# Sheet1.net
KiCad netlist of a schematic drawn in Altium Designer
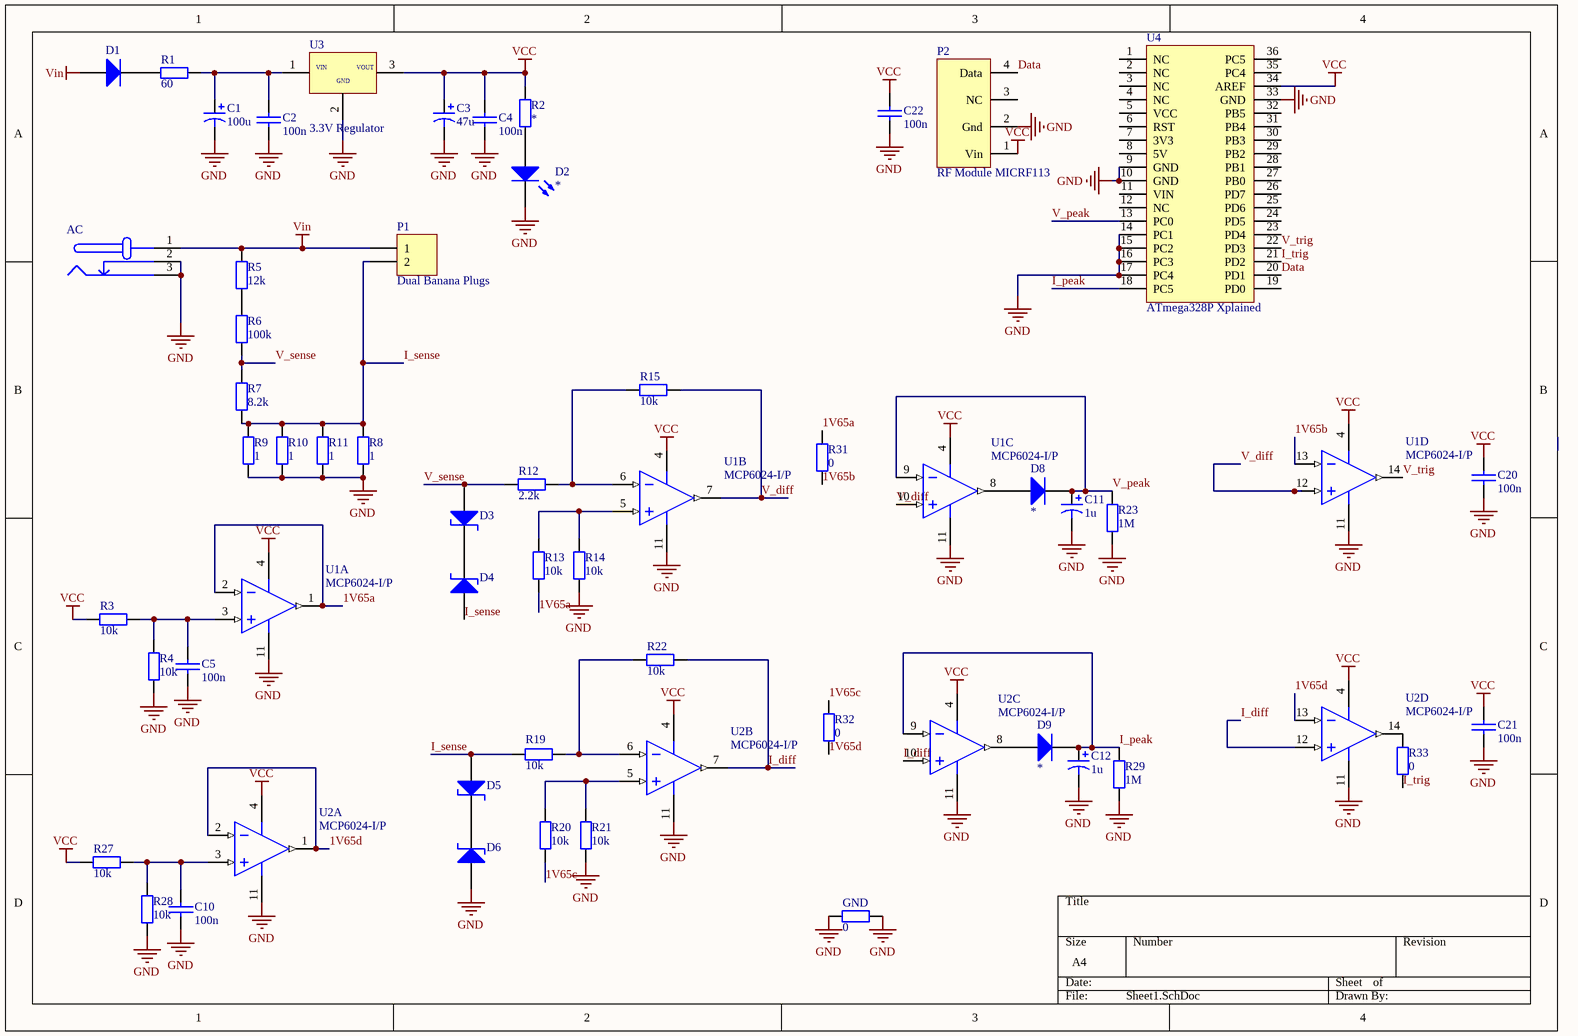
[diagram p0: Sheet1.SchDoc]

(export (version "E")
  (design (tool "Eeschema 10.0.6"))
  (components
    (comp (ref "AC")
      (value "~")
      (footprint "AC-Socket")
      (description "DC socket")
      (libsource (lib "EE209_SCHLibrary") (part "AC Input"))
    )
    (comp (ref "C1")
      (value "100u")
      (footprint "CAP-RAD-3mm Pitch")
      (description "Polarized Capacitor (Axial)")
      (fields (field (name "PUBLISHER") "Altium Limited"))
      (libsource (lib "EE209_SCHLibrary") (part "Cap Pol (22uF-100uF)"))
    )
    (comp (ref "C2")
      (value "100n")
      (footprint "FILM CAP-0.2")
      (description "Capacitor Non Polarised Through Hole")
      (libsource (lib "EE209_SCHLibrary") (part "CAP"))
    )
    (comp (ref "C3")
      (value "47u")
      (footprint "CAP-RAD-3mm Pitch")
      (description "Polarized Capacitor (Axial)")
      (fields (field (name "PUBLISHER") "Altium Limited"))
      (libsource (lib "EE209_SCHLibrary") (part "Cap Pol (22uF-100uF)"))
    )
    (comp (ref "C4")
      (value "100n")
      (footprint "FILM CAP-0.2")
      (description "Capacitor Non Polarised Through Hole")
      (libsource (lib "EE209_SCHLibrary") (part "CAP"))
    )
    (comp (ref "C5")
      (value "100n")
      (footprint "FILM CAP-0.2")
      (description "Capacitor Non Polarised Through Hole")
      (libsource (lib "EE209_SCHLibrary") (part "CAP"))
    )
    (comp (ref "C10")
      (value "100n")
      (footprint "FILM CAP-0.2")
      (description "Capacitor Non Polarised Through Hole")
      (libsource (lib "EE209_SCHLibrary") (part "CAP"))
    )
    (comp (ref "C11")
      (value "1u")
      (footprint "CAP-RAD-2mm Pitch")
      (description "Polarized Capacitor (Axial)")
      (fields (field (name "PUBLISHER") "Altium Limited"))
      (libsource (lib "EE209_SCHLibrary") (part "Cap Pol (1uF-10uF)"))
    )
    (comp (ref "C12")
      (value "1u")
      (footprint "CAP-RAD-2mm Pitch")
      (description "Polarized Capacitor (Axial)")
      (fields (field (name "PUBLISHER") "Altium Limited"))
      (libsource (lib "EE209_SCHLibrary") (part "Cap Pol (1uF-10uF)"))
    )
    (comp (ref "C20")
      (value "100n")
      (footprint "FILM CAP-0.2")
      (description "Capacitor Non Polarised Through Hole")
      (libsource (lib "EE209_SCHLibrary") (part "CAP"))
    )
    (comp (ref "C21")
      (value "100n")
      (footprint "FILM CAP-0.2")
      (description "Capacitor Non Polarised Through Hole")
      (libsource (lib "EE209_SCHLibrary") (part "CAP"))
    )
    (comp (ref "C22")
      (value "100n")
      (footprint "FILM CAP-0.2")
      (description "Capacitor Non Polarised Through Hole")
      (libsource (lib "EE209_SCHLibrary") (part "CAP"))
    )
    (comp (ref "D1")
      (value "~")
      (footprint "AXIAL-DIODE-0.4")
      (fields
        (field (name "MANUFACTURER") "Fairchild Semiconductor")
        (field (name "PUBLISHER") "Altium Limited")
      )
      (libsource (lib "EE209_SCHLibrary") (part "Diode"))
    )
    (comp (ref "D2")
      (value "*")
      (footprint "LED")
      (description "Typical GaAs LED")
      (fields (field (name "MANUFACTURER") "Generic Components") (field (name "PUBLISHER") "Altium Limited"))
      (libsource (lib "EE209_SCHLibrary") (part "LED"))
    )
    (comp (ref "D3")
      (value "~")
      (footprint "AXIAL-DIODE-0.4")
      (description "Zener Diode")
      (libsource (lib "EE209_SCHLibrary") (part "Zener"))
    )
    (comp (ref "D4")
      (value "~")
      (footprint "AXIAL-DIODE-0.4")
      (description "Zener Diode")
      (libsource (lib "EE209_SCHLibrary") (part "Zener"))
    )
    (comp (ref "D5")
      (value "~")
      (footprint "AXIAL-DIODE-0.4")
      (description "Zener Diode")
      (libsource (lib "EE209_SCHLibrary") (part "Zener"))
    )
    (comp (ref "D6")
      (value "~")
      (footprint "AXIAL-DIODE-0.4")
      (description "Zener Diode")
      (libsource (lib "EE209_SCHLibrary") (part "Zener"))
    )
    (comp (ref "D8")
      (value "*")
      (footprint "AXIAL-DIODE-0.4")
      (fields
        (field (name "MANUFACTURER") "Fairchild Semiconductor")
        (field (name "PUBLISHER") "Altium Limited")
      )
      (libsource (lib "EE209_SCHLibrary") (part "Diode"))
    )
    (comp (ref "D9")
      (value "*")
      (footprint "AXIAL-DIODE-0.4")
      (fields
        (field (name "MANUFACTURER") "Fairchild Semiconductor")
        (field (name "PUBLISHER") "Altium Limited")
      )
      (libsource (lib "EE209_SCHLibrary") (part "Diode"))
    )
    (comp (ref "GND")
      (value "0")
      (footprint "AXIAL-0.4")
      (description "Through Hole Resistor")
      (fields (field (name "PUBLISHER") "Altium Limited"))
      (libsource (lib "") (part "Res_1"))
    )
    (comp (ref "P1")
      (value "Dual Banana Plugs")
      (footprint "Dual Banana Plug")
      (description "M6 Holes")
      (fields (field (name "PUBLISHER") "Altium Limited"))
      (libsource (lib "EE209_SCHLibrary") (part "Dual Banana Plugs"))
    )
    (comp (ref "P2")
      (value "RF Module MICRF113")
      (footprint "MICRF113 TX")
      (description "Vertical Mount RF Module")
      (libsource (lib "EE209_SCHLibrary") (part "RF Module"))
    )
    (comp (ref "R1")
      (value "60")
      (footprint "AXIAL-0.4")
      (description "Through Hole Resistor")
      (fields (field (name "PUBLISHER") "Altium Limited"))
      (libsource (lib "") (part "Res_1"))
    )
    (comp (ref "R2")
      (value "*")
      (footprint "AXIAL-0.4")
      (description "Through Hole Resistor")
      (fields (field (name "PUBLISHER") "Altium Limited"))
      (libsource (lib "EE209_SCHLibrary") (part "Res"))
    )
    (comp (ref "R3")
      (value "10k")
      (footprint "AXIAL-0.4")
      (description "Through Hole Resistor")
      (fields (field (name "PUBLISHER") "Altium Limited"))
      (libsource (lib "") (part "Res_1"))
    )
    (comp (ref "R4")
      (value "10k")
      (footprint "AXIAL-0.4")
      (description "Through Hole Resistor")
      (fields (field (name "PUBLISHER") "Altium Limited"))
      (libsource (lib "EE209_SCHLibrary") (part "Res"))
    )
    (comp (ref "R5")
      (value "12k")
      (footprint "AXIAL-0.4")
      (description "Through Hole Resistor")
      (fields (field (name "PUBLISHER") "Altium Limited"))
      (libsource (lib "EE209_SCHLibrary") (part "Res"))
    )
    (comp (ref "R6")
      (value "100k")
      (footprint "AXIAL-0.4")
      (description "Through Hole Resistor")
      (fields (field (name "PUBLISHER") "Altium Limited"))
      (libsource (lib "EE209_SCHLibrary") (part "Res"))
    )
    (comp (ref "R7")
      (value "8.2k")
      (footprint "AXIAL-0.4")
      (description "Through Hole Resistor")
      (fields (field (name "PUBLISHER") "Altium Limited"))
      (libsource (lib "EE209_SCHLibrary") (part "Res"))
    )
    (comp (ref "R8")
      (value "1")
      (footprint "AXIAL-0.4")
      (description "Through Hole Resistor")
      (fields (field (name "PUBLISHER") "Altium Limited"))
      (libsource (lib "EE209_SCHLibrary") (part "Res"))
    )
    (comp (ref "R9")
      (value "1")
      (footprint "AXIAL-0.4")
      (description "Through Hole Resistor")
      (fields (field (name "PUBLISHER") "Altium Limited"))
      (libsource (lib "EE209_SCHLibrary") (part "Res"))
    )
    (comp (ref "R10")
      (value "1")
      (footprint "AXIAL-0.4")
      (description "Through Hole Resistor")
      (fields (field (name "PUBLISHER") "Altium Limited"))
      (libsource (lib "EE209_SCHLibrary") (part "Res"))
    )
    (comp (ref "R11")
      (value "1")
      (footprint "AXIAL-0.4")
      (description "Through Hole Resistor")
      (fields (field (name "PUBLISHER") "Altium Limited"))
      (libsource (lib "EE209_SCHLibrary") (part "Res"))
    )
    (comp (ref "R12")
      (value "2.2k")
      (footprint "AXIAL-0.4")
      (description "Through Hole Resistor")
      (fields (field (name "PUBLISHER") "Altium Limited"))
      (libsource (lib "") (part "Res_1"))
    )
    (comp (ref "R13")
      (value "10k")
      (footprint "AXIAL-0.4")
      (description "Through Hole Resistor")
      (fields (field (name "PUBLISHER") "Altium Limited"))
      (libsource (lib "EE209_SCHLibrary") (part "Res"))
    )
    (comp (ref "R14")
      (value "10k")
      (footprint "AXIAL-0.4")
      (description "Through Hole Resistor")
      (fields (field (name "PUBLISHER") "Altium Limited"))
      (libsource (lib "EE209_SCHLibrary") (part "Res"))
    )
    (comp (ref "R15")
      (value "10k")
      (footprint "AXIAL-0.4")
      (description "Through Hole Resistor")
      (fields (field (name "PUBLISHER") "Altium Limited"))
      (libsource (lib "") (part "Res_1"))
    )
    (comp (ref "R19")
      (value "10k")
      (footprint "AXIAL-0.4")
      (description "Through Hole Resistor")
      (fields (field (name "PUBLISHER") "Altium Limited"))
      (libsource (lib "") (part "Res_1"))
    )
    (comp (ref "R20")
      (value "10k")
      (footprint "AXIAL-0.4")
      (description "Through Hole Resistor")
      (fields (field (name "PUBLISHER") "Altium Limited"))
      (libsource (lib "EE209_SCHLibrary") (part "Res"))
    )
    (comp (ref "R21")
      (value "10k")
      (footprint "AXIAL-0.4")
      (description "Through Hole Resistor")
      (fields (field (name "PUBLISHER") "Altium Limited"))
      (libsource (lib "EE209_SCHLibrary") (part "Res"))
    )
    (comp (ref "R22")
      (value "10k")
      (footprint "AXIAL-0.4")
      (description "Through Hole Resistor")
      (fields (field (name "PUBLISHER") "Altium Limited"))
      (libsource (lib "") (part "Res_1"))
    )
    (comp (ref "R23")
      (value "1M")
      (footprint "AXIAL-0.4")
      (description "Through Hole Resistor")
      (fields (field (name "PUBLISHER") "Altium Limited"))
      (libsource (lib "EE209_SCHLibrary") (part "Res"))
    )
    (comp (ref "R27")
      (value "10k")
      (footprint "AXIAL-0.4")
      (description "Through Hole Resistor")
      (fields (field (name "PUBLISHER") "Altium Limited"))
      (libsource (lib "") (part "Res_1"))
    )
    (comp (ref "R28")
      (value "10k")
      (footprint "AXIAL-0.4")
      (description "Through Hole Resistor")
      (fields (field (name "PUBLISHER") "Altium Limited"))
      (libsource (lib "EE209_SCHLibrary") (part "Res"))
    )
    (comp (ref "R29")
      (value "1M")
      (footprint "AXIAL-0.4")
      (description "Through Hole Resistor")
      (fields (field (name "PUBLISHER") "Altium Limited"))
      (libsource (lib "EE209_SCHLibrary") (part "Res"))
    )
    (comp (ref "R31")
      (value "0")
      (footprint "AXIAL-0.4")
      (description "Through Hole Resistor")
      (fields (field (name "PUBLISHER") "Altium Limited"))
      (libsource (lib "EE209_SCHLibrary") (part "Res"))
    )
    (comp (ref "R32")
      (value "0")
      (footprint "AXIAL-0.4")
      (description "Through Hole Resistor")
      (fields (field (name "PUBLISHER") "Altium Limited"))
      (libsource (lib "EE209_SCHLibrary") (part "Res"))
    )
    (comp (ref "R33")
      (value "0")
      (footprint "AXIAL-0.4")
      (description "Through Hole Resistor")
      (fields (field (name "PUBLISHER") "Altium Limited"))
      (libsource (lib "EE209_SCHLibrary") (part "Res"))
    )
    (comp (ref "U1")
      (value "MCP6024-I/P")
      (footprint "DIP-14")
      (description "Rail-to-Rail Input/Output, 10 MHz Operational Amplifier, 14-Pin PDIP, Industrial Temperature")
      (fields (field (name "PUBLISHER") "Altium Limited"))
      (libsource (lib "EE209_SCHLibrary") (part "MCP6024-I/P"))
    )
    (comp (ref "U2")
      (value "MCP6024-I/P")
      (footprint "DIP-14")
      (description "Rail-to-Rail Input/Output, 10 MHz Operational Amplifier, 14-Pin PDIP, Industrial Temperature")
      (fields (field (name "PUBLISHER") "Altium Limited"))
      (libsource (lib "EE209_SCHLibrary") (part "MCP6024-I/P"))
    )
    (comp (ref "U3")
      (value "3.3V Regulator")
      (footprint "TO-92")
      (libsource (lib "EE209_SCHLibrary") (part "LP2950-33"))
    )
    (comp (ref "U4")
      (value "ATmega328P Xplained")
      (footprint "ATmeg328P Xplained")
      (description "Header, 18-Pin, Dual row")
      (fields (field (name "PUBLISHER") "Altium Limited"))
      (libsource (lib "EE209_SCHLibrary") (part "ATmega328P Xplained"))
    )
  )
  (nets
    (net (code "1") (name "/1V65a") (class "Default")
      (node (ref "R13") (pin "1") (pinfunction "1_1") (pintype "passive"))
      (node (ref "R31") (pin "2") (pinfunction "2_2") (pintype "passive"))
      (node (ref "U1") (pin "1") (pinfunction "VOUTA_1") (pintype "output"))
      (node (ref "U1") (pin "2") (pinfunction "VINA-_2") (pintype "input"))
    )
    (net (code "2") (name "/1V65b") (class "Default")
      (node (ref "R31") (pin "1") (pinfunction "1_1") (pintype "passive"))
      (node (ref "U1") (pin "13") (pinfunction "VIND-_13") (pintype "input"))
    )
    (net (code "3") (name "/1V65c") (class "Default")
      (node (ref "R20") (pin "1") (pinfunction "1_1") (pintype "passive"))
      (node (ref "R32") (pin "2") (pinfunction "2_2") (pintype "passive"))
    )
    (net (code "4") (name "/1V65d") (class "Default")
      (node (ref "R32") (pin "1") (pinfunction "1_1") (pintype "passive"))
      (node (ref "U2") (pin "1") (pinfunction "VOUTA_1") (pintype "output"))
      (node (ref "U2") (pin "13") (pinfunction "VIND-_13") (pintype "input"))
      (node (ref "U2") (pin "2") (pinfunction "VINA-_2") (pintype "input"))
    )
    (net (code "5") (name "/Data") (class "Default")
      (node (ref "P2") (pin "4") (pinfunction "Data_4") (pintype "passive"))
      (node (ref "U4") (pin "20") (pinfunction "PD1_20") (pintype "passive"))
    )
    (net (code "6") (name "/I_diff") (class "Default")
      (node (ref "R22") (pin "2") (pinfunction "2_2") (pintype "passive"))
      (node (ref "U2") (pin "10") (pinfunction "VINC+_10") (pintype "input"))
      (node (ref "U2") (pin "12") (pinfunction "VIND+_12") (pintype "input"))
      (node (ref "U2") (pin "7") (pinfunction "VOUTB_7") (pintype "output"))
    )
    (net (code "7") (name "/I_peak") (class "Default")
      (node (ref "C12") (pin "1") (pinfunction "1_1") (pintype "passive"))
      (node (ref "D9") (pin "2") (pinfunction "K_2") (pintype "passive"))
      (node (ref "R29") (pin "2") (pinfunction "2_2") (pintype "passive"))
      (node (ref "U2") (pin "9") (pinfunction "VINC-_9") (pintype "input"))
      (node (ref "U4") (pin "18") (pinfunction "PC5_18") (pintype "passive"))
    )
    (net (code "8") (name "/I_sense") (class "Default")
      (node (ref "D4") (pin "1") (pinfunction "A_1") (pintype "passive"))
      (node (ref "D5") (pin "1") (pinfunction "A_1") (pintype "passive"))
      (node (ref "P1") (pin "2") (pinfunction "2_2") (pintype "passive"))
      (node (ref "R10") (pin "2") (pinfunction "2_2") (pintype "passive"))
      (node (ref "R11") (pin "2") (pinfunction "2_2") (pintype "passive"))
      (node (ref "R19") (pin "1") (pinfunction "1_1") (pintype "passive"))
      (node (ref "R7") (pin "1") (pinfunction "1_1") (pintype "passive"))
      (node (ref "R8") (pin "2") (pinfunction "2_2") (pintype "passive"))
      (node (ref "R9") (pin "2") (pinfunction "2_2") (pintype "passive"))
    )
    (net (code "9") (name "/I_trig") (class "Default")
      (node (ref "R33") (pin "1") (pinfunction "1_1") (pintype "passive"))
      (node (ref "U4") (pin "21") (pinfunction "PD2_21") (pintype "passive"))
    )
    (net (code "10") (name "/V_diff") (class "Default")
      (node (ref "R15") (pin "2") (pinfunction "2_2") (pintype "passive"))
      (node (ref "U1") (pin "10") (pinfunction "VINC+_10") (pintype "input"))
      (node (ref "U1") (pin "12") (pinfunction "VIND+_12") (pintype "input"))
      (node (ref "U1") (pin "7") (pinfunction "VOUTB_7") (pintype "output"))
    )
    (net (code "11") (name "/V_peak") (class "Default")
      (node (ref "C11") (pin "1") (pinfunction "1_1") (pintype "passive"))
      (node (ref "D8") (pin "2") (pinfunction "K_2") (pintype "passive"))
      (node (ref "R23") (pin "2") (pinfunction "2_2") (pintype "passive"))
      (node (ref "U1") (pin "9") (pinfunction "VINC-_9") (pintype "input"))
      (node (ref "U4") (pin "13") (pinfunction "PC0_13") (pintype "passive"))
    )
    (net (code "12") (name "/V_sense") (class "Default")
      (node (ref "D3") (pin "1") (pinfunction "A_1") (pintype "passive"))
      (node (ref "R12") (pin "1") (pinfunction "1_1") (pintype "passive"))
      (node (ref "R6") (pin "1") (pinfunction "1_1") (pintype "passive"))
      (node (ref "R7") (pin "2") (pinfunction "2_2") (pintype "passive"))
    )
    (net (code "13") (name "/V_trig") (class "Default")
      (node (ref "U1") (pin "14") (pinfunction "VOUTD_14") (pintype "output"))
      (node (ref "U4") (pin "22") (pinfunction "PD3_22") (pintype "passive"))
    )
    (net (code "14") (name "GND") (class "Default")
      (node (ref "AC") (pin "2") (pinfunction "GND_ALT_2") (pintype "power_in"))
      (node (ref "AC") (pin "3") (pinfunction "GND_3") (pintype "power_in"))
      (node (ref "C1") (pin "2") (pinfunction "2_2") (pintype "passive"))
      (node (ref "C10") (pin "2") (pinfunction "2_2") (pintype "passive"))
      (node (ref "C11") (pin "2") (pinfunction "2_2") (pintype "passive"))
      (node (ref "C12") (pin "2") (pinfunction "2_2") (pintype "passive"))
      (node (ref "C2") (pin "2") (pinfunction "2_2") (pintype "passive"))
      (node (ref "C20") (pin "2") (pinfunction "2_2") (pintype "passive"))
      (node (ref "C21") (pin "2") (pinfunction "2_2") (pintype "passive"))
      (node (ref "C22") (pin "2") (pinfunction "2_2") (pintype "passive"))
      (node (ref "C3") (pin "2") (pinfunction "2_2") (pintype "passive"))
      (node (ref "C4") (pin "2") (pinfunction "2_2") (pintype "passive"))
      (node (ref "C5") (pin "2") (pinfunction "2_2") (pintype "passive"))
      (node (ref "D2") (pin "2") (pinfunction "K_2") (pintype "passive"))
      (node (ref "D6") (pin "1") (pinfunction "A_1") (pintype "passive"))
      (node (ref "GND") (pin "1") (pinfunction "1_1") (pintype "passive"))
      (node (ref "GND") (pin "2") (pinfunction "2_2") (pintype "passive"))
      (node (ref "P2") (pin "2") (pinfunction "Gnd_2") (pintype "passive"))
      (node (ref "R10") (pin "1") (pinfunction "1_1") (pintype "passive"))
      (node (ref "R11") (pin "1") (pinfunction "1_1") (pintype "passive"))
      (node (ref "R14") (pin "1") (pinfunction "1_1") (pintype "passive"))
      (node (ref "R21") (pin "1") (pinfunction "1_1") (pintype "passive"))
      (node (ref "R23") (pin "1") (pinfunction "1_1") (pintype "passive"))
      (node (ref "R28") (pin "1") (pinfunction "1_1") (pintype "passive"))
      (node (ref "R29") (pin "1") (pinfunction "1_1") (pintype "passive"))
      (node (ref "R4") (pin "1") (pinfunction "1_1") (pintype "passive"))
      (node (ref "R8") (pin "1") (pinfunction "1_1") (pintype "passive"))
      (node (ref "R9") (pin "1") (pinfunction "1_1") (pintype "passive"))
      (node (ref "U1") (pin "11") (pinfunction "VSS_11") (pintype "power_in"))
      (node (ref "U2") (pin "11") (pinfunction "VSS_11") (pintype "power_in"))
      (node (ref "U3") (pin "2") (pinfunction "GND_2") (pintype "passive"))
      (node (ref "U4") (pin "10") (pinfunction "GND_10") (pintype "power_in"))
      (node (ref "U4") (pin "14") (pinfunction "PC1_14") (pintype "passive"))
      (node (ref "U4") (pin "15") (pinfunction "PC2_15") (pintype "passive"))
      (node (ref "U4") (pin "16") (pinfunction "PC3_16") (pintype "passive"))
      (node (ref "U4") (pin "17") (pinfunction "PC4_17") (pintype "passive"))
      (node (ref "U4") (pin "33") (pinfunction "GND_33") (pintype "passive"))
      (node (ref "U4") (pin "9") (pinfunction "GND_9") (pintype "power_in"))
    )
    (net (code "15") (name "Net-(D1-K)") (class "Default")
      (node (ref "D1") (pin "2") (pinfunction "K_2") (pintype "passive"))
      (node (ref "R1") (pin "1") (pinfunction "1_1") (pintype "passive"))
    )
    (net (code "16") (name "Net-(D2-A)") (class "Default")
      (node (ref "D2") (pin "1") (pinfunction "A_1") (pintype "passive"))
      (node (ref "R2") (pin "1") (pinfunction "1_1") (pintype "passive"))
    )
    (net (code "17") (name "Net-(D3-K)") (class "Default")
      (node (ref "D3") (pin "2") (pinfunction "K_2") (pintype "passive"))
      (node (ref "D4") (pin "2") (pinfunction "K_2") (pintype "passive"))
    )
    (net (code "18") (name "Net-(D5-K)") (class "Default")
      (node (ref "D5") (pin "2") (pinfunction "K_2") (pintype "passive"))
      (node (ref "D6") (pin "2") (pinfunction "K_2") (pintype "passive"))
    )
    (net (code "19") (name "Net-(D8-A)") (class "Default")
      (node (ref "D8") (pin "1") (pinfunction "A_1") (pintype "passive"))
      (node (ref "U1") (pin "8") (pinfunction "VOUTC_8") (pintype "output"))
    )
    (net (code "20") (name "Net-(D9-A)") (class "Default")
      (node (ref "D9") (pin "1") (pinfunction "A_1") (pintype "passive"))
      (node (ref "U2") (pin "8") (pinfunction "VOUTC_8") (pintype "output"))
    )
    (net (code "21") (name "Net-(R5-Pad1)") (class "Default")
      (node (ref "R5") (pin "1") (pinfunction "1_1") (pintype "passive"))
      (node (ref "R6") (pin "2") (pinfunction "2_2") (pintype "passive"))
    )
    (net (code "22") (name "Net-(U1A-VINA+)") (class "Default")
      (node (ref "C5") (pin "1") (pinfunction "1_1") (pintype "passive"))
      (node (ref "R3") (pin "2") (pinfunction "2_2") (pintype "passive"))
      (node (ref "R4") (pin "2") (pinfunction "2_2") (pintype "passive"))
      (node (ref "U1") (pin "3") (pinfunction "VINA+_3") (pintype "input"))
    )
    (net (code "23") (name "Net-(U1B-VINB+)") (class "Default")
      (node (ref "R13") (pin "2") (pinfunction "2_2") (pintype "passive"))
      (node (ref "R14") (pin "2") (pinfunction "2_2") (pintype "passive"))
      (node (ref "U1") (pin "5") (pinfunction "VINB+_5") (pintype "input"))
    )
    (net (code "24") (name "Net-(U1B-VINB-)") (class "Default")
      (node (ref "R12") (pin "2") (pinfunction "2_2") (pintype "passive"))
      (node (ref "R15") (pin "1") (pinfunction "1_1") (pintype "passive"))
      (node (ref "U1") (pin "6") (pinfunction "VINB-_6") (pintype "input"))
    )
    (net (code "25") (name "Net-(U2A-VINA+)") (class "Default")
      (node (ref "C10") (pin "1") (pinfunction "1_1") (pintype "passive"))
      (node (ref "R27") (pin "2") (pinfunction "2_2") (pintype "passive"))
      (node (ref "R28") (pin "2") (pinfunction "2_2") (pintype "passive"))
      (node (ref "U2") (pin "3") (pinfunction "VINA+_3") (pintype "input"))
    )
    (net (code "26") (name "Net-(U2B-VINB+)") (class "Default")
      (node (ref "R20") (pin "2") (pinfunction "2_2") (pintype "passive"))
      (node (ref "R21") (pin "2") (pinfunction "2_2") (pintype "passive"))
      (node (ref "U2") (pin "5") (pinfunction "VINB+_5") (pintype "input"))
    )
    (net (code "27") (name "Net-(U2B-VINB-)") (class "Default")
      (node (ref "R19") (pin "2") (pinfunction "2_2") (pintype "passive"))
      (node (ref "R22") (pin "1") (pinfunction "1_1") (pintype "passive"))
      (node (ref "U2") (pin "6") (pinfunction "VINB-_6") (pintype "input"))
    )
    (net (code "28") (name "Net-(U2D-VOUTD)") (class "Default")
      (node (ref "R33") (pin "2") (pinfunction "2_2") (pintype "passive"))
      (node (ref "U2") (pin "14") (pinfunction "VOUTD_14") (pintype "output"))
    )
    (net (code "29") (name "Net-(U3-INPUT)") (class "Default")
      (node (ref "C1") (pin "1") (pinfunction "1_1") (pintype "passive"))
      (node (ref "C2") (pin "1") (pinfunction "1_1") (pintype "passive"))
      (node (ref "R1") (pin "2") (pinfunction "2_2") (pintype "passive"))
      (node (ref "U3") (pin "1") (pinfunction "INPUT_1") (pintype "passive"))
    )
    (net (code "30") (name "VCC") (class "Default")
      (node (ref "C20") (pin "1") (pinfunction "1_1") (pintype "passive"))
      (node (ref "C21") (pin "1") (pinfunction "1_1") (pintype "passive"))
      (node (ref "C22") (pin "1") (pinfunction "1_1") (pintype "passive"))
      (node (ref "C3") (pin "1") (pinfunction "1_1") (pintype "passive"))
      (node (ref "C4") (pin "1") (pinfunction "1_1") (pintype "passive"))
      (node (ref "P2") (pin "1") (pinfunction "Vin_1") (pintype "passive"))
      (node (ref "R2") (pin "2") (pinfunction "2_2") (pintype "passive"))
      (node (ref "R27") (pin "1") (pinfunction "1_1") (pintype "passive"))
      (node (ref "R3") (pin "1") (pinfunction "1_1") (pintype "passive"))
      (node (ref "U1") (pin "4") (pinfunction "VDD_4") (pintype "power_in"))
      (node (ref "U2") (pin "4") (pinfunction "VDD_4") (pintype "power_in"))
      (node (ref "U3") (pin "3") (pinfunction "OUTPUT_3") (pintype "passive"))
      (node (ref "U4") (pin "34") (pinfunction "AREF_34") (pintype "passive"))
    )
    (net (code "31") (name "Vin") (class "Default")
      (node (ref "AC") (pin "1") (pinfunction "VCC_1") (pintype "power_in"))
      (node (ref "D1") (pin "1") (pinfunction "A_1") (pintype "passive"))
      (node (ref "P1") (pin "1") (pinfunction "1_1") (pintype "passive"))
      (node (ref "R5") (pin "2") (pinfunction "2_2") (pintype "passive"))
    )
    (net (code "32") (name "unconnected-(P2-NC-Pad3)") (class "Default")
      (node (ref "P2") (pin "3") (pinfunction "NC_3") (pintype "passive"))
    )
    (net (code "33") (name "unconnected-(U1B-VDD-Pad4)") (class "Default")
      (node (ref "U1") (pin "4") (pinfunction "VDD_4") (pintype "power_in"))
    )
    (net (code "34") (name "unconnected-(U4-3V3-Pad7)") (class "Default")
      (node (ref "U4") (pin "7") (pinfunction "3V3_7") (pintype "passive"))
    )
    (net (code "35") (name "unconnected-(U4-5V-Pad8)") (class "Default")
      (node (ref "U4") (pin "8") (pinfunction "5V_8") (pintype "power_in"))
    )
    (net (code "36") (name "unconnected-(U4-NC-Pad1)") (class "Default")
      (node (ref "U4") (pin "1") (pinfunction "NC_1") (pintype "passive"))
    )
    (net (code "37") (name "unconnected-(U4-NC-Pad2)") (class "Default")
      (node (ref "U4") (pin "2") (pinfunction "NC_2") (pintype "passive"))
    )
    (net (code "38") (name "unconnected-(U4-NC-Pad3)") (class "Default")
      (node (ref "U4") (pin "3") (pinfunction "NC_3") (pintype "passive"))
    )
    (net (code "39") (name "unconnected-(U4-NC-Pad4)") (class "Default")
      (node (ref "U4") (pin "4") (pinfunction "NC_4") (pintype "passive"))
    )
    (net (code "40") (name "unconnected-(U4-NC-Pad12)") (class "Default")
      (node (ref "U4") (pin "12") (pinfunction "NC_12") (pintype "passive"))
    )
    (net (code "41") (name "unconnected-(U4-PB0-Pad27)") (class "Default")
      (node (ref "U4") (pin "27") (pinfunction "PB0_27") (pintype "passive"))
    )
    (net (code "42") (name "unconnected-(U4-PB1-Pad28)") (class "Default")
      (node (ref "U4") (pin "28") (pinfunction "PB1_28") (pintype "passive"))
    )
    (net (code "43") (name "unconnected-(U4-PB2-Pad29)") (class "Default")
      (node (ref "U4") (pin "29") (pinfunction "PB2_29") (pintype "passive"))
    )
    (net (code "44") (name "unconnected-(U4-PB3-Pad30)") (class "Default")
      (node (ref "U4") (pin "30") (pinfunction "PB3_30") (pintype "passive"))
    )
    (net (code "45") (name "unconnected-(U4-PB4-Pad31)") (class "Default")
      (node (ref "U4") (pin "31") (pinfunction "PB4_31") (pintype "passive"))
    )
    (net (code "46") (name "unconnected-(U4-PB5-Pad32)") (class "Default")
      (node (ref "U4") (pin "32") (pinfunction "PB5_32") (pintype "passive"))
    )
    (net (code "47") (name "unconnected-(U4-PC4-Pad35)") (class "Default")
      (node (ref "U4") (pin "35") (pinfunction "PC4_35") (pintype "passive"))
    )
    (net (code "48") (name "unconnected-(U4-PC5-Pad36)") (class "Default")
      (node (ref "U4") (pin "36") (pinfunction "PC5_36") (pintype "passive"))
    )
    (net (code "49") (name "unconnected-(U4-PD0-Pad19)") (class "Default")
      (node (ref "U4") (pin "19") (pinfunction "PD0_19") (pintype "passive"))
    )
    (net (code "50") (name "unconnected-(U4-PD4-Pad23)") (class "Default")
      (node (ref "U4") (pin "23") (pinfunction "PD4_23") (pintype "passive"))
    )
    (net (code "51") (name "unconnected-(U4-PD5-Pad24)") (class "Default")
      (node (ref "U4") (pin "24") (pinfunction "PD5_24") (pintype "passive"))
    )
    (net (code "52") (name "unconnected-(U4-PD6-Pad25)") (class "Default")
      (node (ref "U4") (pin "25") (pinfunction "PD6_25") (pintype "passive"))
    )
    (net (code "53") (name "unconnected-(U4-PD7-Pad26)") (class "Default")
      (node (ref "U4") (pin "26") (pinfunction "PD7_26") (pintype "passive"))
    )
    (net (code "54") (name "unconnected-(U4-RST-Pad6)") (class "Default")
      (node (ref "U4") (pin "6") (pinfunction "RST_6") (pintype "passive"))
    )
    (net (code "55") (name "unconnected-(U4-VCC-Pad5)") (class "Default")
      (node (ref "U4") (pin "5") (pinfunction "VCC_5") (pintype "power_in"))
    )
    (net (code "56") (name "unconnected-(U4-VIN-Pad11)") (class "Default")
      (node (ref "U4") (pin "11") (pinfunction "VIN_11") (pintype "power_in"))
    )
  )
)
